# TASK8.net
KiCad netlist of a schematic drawn in EAGLE
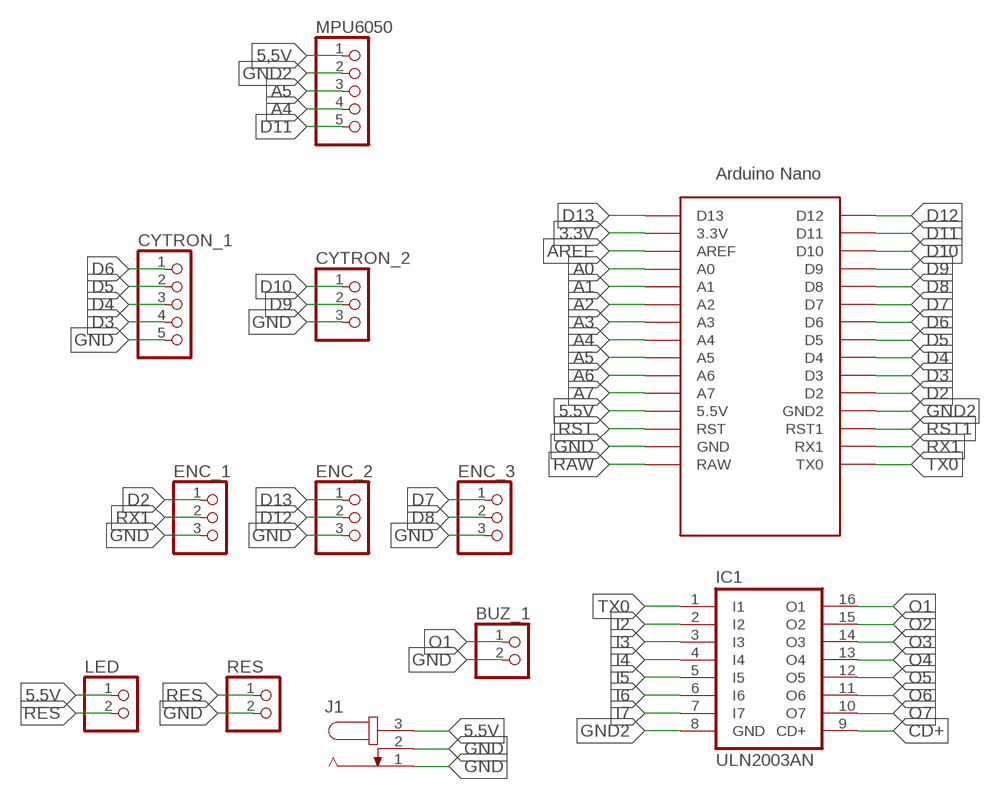
[diagram p0: schematic, sheet 1]

(export (version "E")
  (design (tool "Eeschema 10.0.6"))
  (components
    (comp (ref "BUZ_1")
      (value "PINHD-1X2")
      (footprint "eagle-import:1X02")
      (libsource (lib "eagle-import") (part "PINHD-1X2"))
    )
    (comp (ref "CYTRON_1")
      (value "PINHD-1X5")
      (footprint "eagle-import:1X05")
      (libsource (lib "eagle-import") (part "PINHD-1X5"))
    )
    (comp (ref "CYTRON_2")
      (value "PINHD-1X3")
      (footprint "eagle-import:1X03")
      (libsource (lib "eagle-import") (part "PINHD-1X3"))
    )
    (comp (ref "ENC_1")
      (value "PINHD-1X3")
      (footprint "eagle-import:1X03")
      (libsource (lib "eagle-import") (part "PINHD-1X3"))
    )
    (comp (ref "ENC_2")
      (value "PINHD-1X3")
      (footprint "eagle-import:1X03")
      (libsource (lib "eagle-import") (part "PINHD-1X3"))
    )
    (comp (ref "ENC_3")
      (value "PINHD-1X3")
      (footprint "eagle-import:1X03")
      (libsource (lib "eagle-import") (part "PINHD-1X3"))
    )
    (comp (ref "IC1")
      (value "ULN2003AN")
      (footprint "eagle-import:DIL16")
      (libsource (lib "eagle-import") (part "ULN2003AN"))
    )
    (comp (ref "J1")
      (value "JACK-PLUG0")
      (footprint "eagle-import:SPC4077")
      (libsource (lib "eagle-import") (part "JACK-PLUG0"))
    )
    (comp (ref "LED")
      (value "PINHD-1X2")
      (footprint "eagle-import:1X02")
      (libsource (lib "eagle-import") (part "PINHD-1X2"))
    )
    (comp (ref "MPU6050")
      (value "PINHD-1X5")
      (footprint "eagle-import:1X05")
      (libsource (lib "eagle-import") (part "PINHD-1X5"))
    )
    (comp (ref "RES")
      (value "PINHD-1X2")
      (footprint "eagle-import:1X02")
      (libsource (lib "eagle-import") (part "PINHD-1X2"))
    )
    (comp (ref "U$1")
      (value "ARDUINO_NANO")
      (footprint "eagle-import:NANO")
      (libsource (lib "eagle-import") (part "ARDUINO_NANO"))
    )
  )
  (nets
    (net (code "1") (name "3.3V") (class "Default")
      (node (ref "U$1") (pin "3.3V") (pinfunction "3.3V_3.3V") (pintype "bidirectional"))
    )
    (net (code "2") (name "5,5V") (class "Default")
      (node (ref "MPU6050") (pin "1") (pinfunction "1_1") (pintype "passive"))
    )
    (net (code "3") (name "5.5V") (class "Default")
      (node (ref "J1") (pin "3") (pinfunction "3_3") (pintype "passive"))
      (node (ref "LED") (pin "1") (pinfunction "1_1") (pintype "passive"))
      (node (ref "U$1") (pin "5V") (pinfunction "5.5V_5V") (pintype "bidirectional"))
    )
    (net (code "4") (name "A0") (class "Default")
      (node (ref "U$1") (pin "A0") (pinfunction "A0_A0") (pintype "bidirectional"))
    )
    (net (code "5") (name "A1") (class "Default")
      (node (ref "U$1") (pin "A1") (pinfunction "A1_A1") (pintype "bidirectional"))
    )
    (net (code "6") (name "A2") (class "Default")
      (node (ref "U$1") (pin "A2") (pinfunction "A2_A2") (pintype "bidirectional"))
    )
    (net (code "7") (name "A3") (class "Default")
      (node (ref "U$1") (pin "A3") (pinfunction "A3_A3") (pintype "bidirectional"))
    )
    (net (code "8") (name "A4") (class "Default")
      (node (ref "MPU6050") (pin "4") (pinfunction "4_4") (pintype "passive"))
      (node (ref "U$1") (pin "A4") (pinfunction "A4_A4") (pintype "bidirectional"))
    )
    (net (code "9") (name "A5") (class "Default")
      (node (ref "MPU6050") (pin "3") (pinfunction "3_3") (pintype "passive"))
      (node (ref "U$1") (pin "A5") (pinfunction "A5_A5") (pintype "bidirectional"))
    )
    (net (code "10") (name "A6") (class "Default")
      (node (ref "U$1") (pin "A6") (pinfunction "A6_A6") (pintype "bidirectional"))
    )
    (net (code "11") (name "A7") (class "Default")
      (node (ref "U$1") (pin "A7") (pinfunction "A7_A7") (pintype "bidirectional"))
    )
    (net (code "12") (name "AREF") (class "Default")
      (node (ref "U$1") (pin "AREF") (pinfunction "AREF_AREF") (pintype "bidirectional"))
    )
    (net (code "13") (name "CD+") (class "Default")
      (node (ref "IC1") (pin "9") (pinfunction "CD+_9") (pintype "passive"))
    )
    (net (code "14") (name "D2") (class "Default")
      (node (ref "ENC_1") (pin "1") (pinfunction "1_1") (pintype "passive"))
      (node (ref "U$1") (pin "D2") (pinfunction "D2_D2") (pintype "bidirectional"))
    )
    (net (code "15") (name "D3") (class "Default")
      (node (ref "CYTRON_1") (pin "4") (pinfunction "4_4") (pintype "passive"))
      (node (ref "U$1") (pin "D3") (pinfunction "D3_D3") (pintype "bidirectional"))
    )
    (net (code "16") (name "D4") (class "Default")
      (node (ref "CYTRON_1") (pin "3") (pinfunction "3_3") (pintype "passive"))
      (node (ref "U$1") (pin "D4") (pinfunction "D4_D4") (pintype "bidirectional"))
    )
    (net (code "17") (name "D5") (class "Default")
      (node (ref "CYTRON_1") (pin "2") (pinfunction "2_2") (pintype "passive"))
      (node (ref "U$1") (pin "D5") (pinfunction "D5_D5") (pintype "bidirectional"))
    )
    (net (code "18") (name "D6") (class "Default")
      (node (ref "CYTRON_1") (pin "1") (pinfunction "1_1") (pintype "passive"))
      (node (ref "U$1") (pin "D6") (pinfunction "D6_D6") (pintype "bidirectional"))
    )
    (net (code "19") (name "D7") (class "Default")
      (node (ref "ENC_3") (pin "1") (pinfunction "1_1") (pintype "passive"))
      (node (ref "U$1") (pin "D7") (pinfunction "D7_D7") (pintype "bidirectional"))
    )
    (net (code "20") (name "D8") (class "Default")
      (node (ref "ENC_3") (pin "2") (pinfunction "2_2") (pintype "passive"))
      (node (ref "U$1") (pin "D8") (pinfunction "D8_D8") (pintype "bidirectional"))
    )
    (net (code "21") (name "D9") (class "Default")
      (node (ref "CYTRON_2") (pin "2") (pinfunction "2_2") (pintype "passive"))
      (node (ref "U$1") (pin "D9") (pinfunction "D9_D9") (pintype "bidirectional"))
    )
    (net (code "22") (name "D10") (class "Default")
      (node (ref "CYTRON_2") (pin "1") (pinfunction "1_1") (pintype "passive"))
      (node (ref "U$1") (pin "D10") (pinfunction "D10_D10") (pintype "bidirectional"))
    )
    (net (code "23") (name "D11") (class "Default")
      (node (ref "MPU6050") (pin "5") (pinfunction "5_5") (pintype "passive"))
      (node (ref "U$1") (pin "D11") (pinfunction "D11_D11") (pintype "bidirectional"))
    )
    (net (code "24") (name "D12") (class "Default")
      (node (ref "ENC_2") (pin "2") (pinfunction "2_2") (pintype "passive"))
      (node (ref "U$1") (pin "D12") (pinfunction "D12_D12") (pintype "bidirectional"))
    )
    (net (code "25") (name "D13") (class "Default")
      (node (ref "ENC_2") (pin "1") (pinfunction "1_1") (pintype "passive"))
      (node (ref "U$1") (pin "D13") (pinfunction "D13_D13") (pintype "bidirectional"))
    )
    (net (code "26") (name "GND") (class "Default")
      (node (ref "BUZ_1") (pin "2") (pinfunction "2_2") (pintype "passive"))
      (node (ref "CYTRON_1") (pin "5") (pinfunction "5_5") (pintype "passive"))
      (node (ref "CYTRON_2") (pin "3") (pinfunction "3_3") (pintype "passive"))
      (node (ref "ENC_1") (pin "3") (pinfunction "3_3") (pintype "passive"))
      (node (ref "ENC_2") (pin "3") (pinfunction "3_3") (pintype "passive"))
      (node (ref "ENC_3") (pin "3") (pinfunction "3_3") (pintype "passive"))
      (node (ref "J1") (pin "1") (pinfunction "1_1") (pintype "passive"))
      (node (ref "J1") (pin "2") (pinfunction "2_2") (pintype "passive"))
      (node (ref "RES") (pin "2") (pinfunction "2_2") (pintype "passive"))
      (node (ref "U$1") (pin "GND") (pinfunction "GND_GND") (pintype "bidirectional"))
    )
    (net (code "27") (name "GND2") (class "Default")
      (node (ref "IC1") (pin "8") (pinfunction "GND_8") (pintype "power_in"))
      (node (ref "MPU6050") (pin "2") (pinfunction "2_2") (pintype "passive"))
      (node (ref "U$1") (pin "GND1") (pinfunction "GND2_GND1") (pintype "bidirectional"))
    )
    (net (code "28") (name "I2") (class "Default")
      (node (ref "IC1") (pin "2") (pinfunction "I2_2") (pintype "input"))
    )
    (net (code "29") (name "I3") (class "Default")
      (node (ref "IC1") (pin "3") (pinfunction "I3_3") (pintype "input"))
    )
    (net (code "30") (name "I4") (class "Default")
      (node (ref "IC1") (pin "4") (pinfunction "I4_4") (pintype "input"))
    )
    (net (code "31") (name "I5") (class "Default")
      (node (ref "IC1") (pin "5") (pinfunction "I5_5") (pintype "input"))
    )
    (net (code "32") (name "I6") (class "Default")
      (node (ref "IC1") (pin "6") (pinfunction "I6_6") (pintype "input"))
    )
    (net (code "33") (name "I7") (class "Default")
      (node (ref "IC1") (pin "7") (pinfunction "I7_7") (pintype "input"))
    )
    (net (code "34") (name "O1") (class "Default")
      (node (ref "BUZ_1") (pin "1") (pinfunction "1_1") (pintype "passive"))
      (node (ref "IC1") (pin "16") (pinfunction "O1_16") (pintype "open_collector"))
    )
    (net (code "35") (name "O2") (class "Default")
      (node (ref "IC1") (pin "15") (pinfunction "O2_15") (pintype "open_collector"))
    )
    (net (code "36") (name "O3") (class "Default")
      (node (ref "IC1") (pin "14") (pinfunction "O3_14") (pintype "open_collector"))
    )
    (net (code "37") (name "O4") (class "Default")
      (node (ref "IC1") (pin "13") (pinfunction "O4_13") (pintype "open_collector"))
    )
    (net (code "38") (name "O5") (class "Default")
      (node (ref "IC1") (pin "12") (pinfunction "O5_12") (pintype "open_collector"))
    )
    (net (code "39") (name "O6") (class "Default")
      (node (ref "IC1") (pin "11") (pinfunction "O6_11") (pintype "open_collector"))
    )
    (net (code "40") (name "O7") (class "Default")
      (node (ref "IC1") (pin "10") (pinfunction "O7_10") (pintype "open_collector"))
    )
    (net (code "41") (name "RAW") (class "Default")
      (node (ref "U$1") (pin "RAW") (pinfunction "RAW_RAW") (pintype "bidirectional"))
    )
    (net (code "42") (name "RES") (class "Default")
      (node (ref "LED") (pin "2") (pinfunction "2_2") (pintype "passive"))
      (node (ref "RES") (pin "1") (pinfunction "1_1") (pintype "passive"))
    )
    (net (code "43") (name "RST") (class "Default")
      (node (ref "U$1") (pin "RST") (pinfunction "RST_RST") (pintype "bidirectional"))
    )
    (net (code "44") (name "RST1") (class "Default")
      (node (ref "U$1") (pin "RST1") (pinfunction "RST1_RST1") (pintype "bidirectional"))
    )
    (net (code "45") (name "RX1") (class "Default")
      (node (ref "ENC_1") (pin "2") (pinfunction "2_2") (pintype "passive"))
      (node (ref "U$1") (pin "RX1") (pinfunction "RX1_RX1") (pintype "bidirectional"))
    )
    (net (code "46") (name "TX0") (class "Default")
      (node (ref "IC1") (pin "1") (pinfunction "I1_1") (pintype "input"))
      (node (ref "U$1") (pin "TX0") (pinfunction "TX0_TX0") (pintype "bidirectional"))
    )
  )
)
